# cdh.net
KiCad netlist of a schematic drawn in Altium Designer
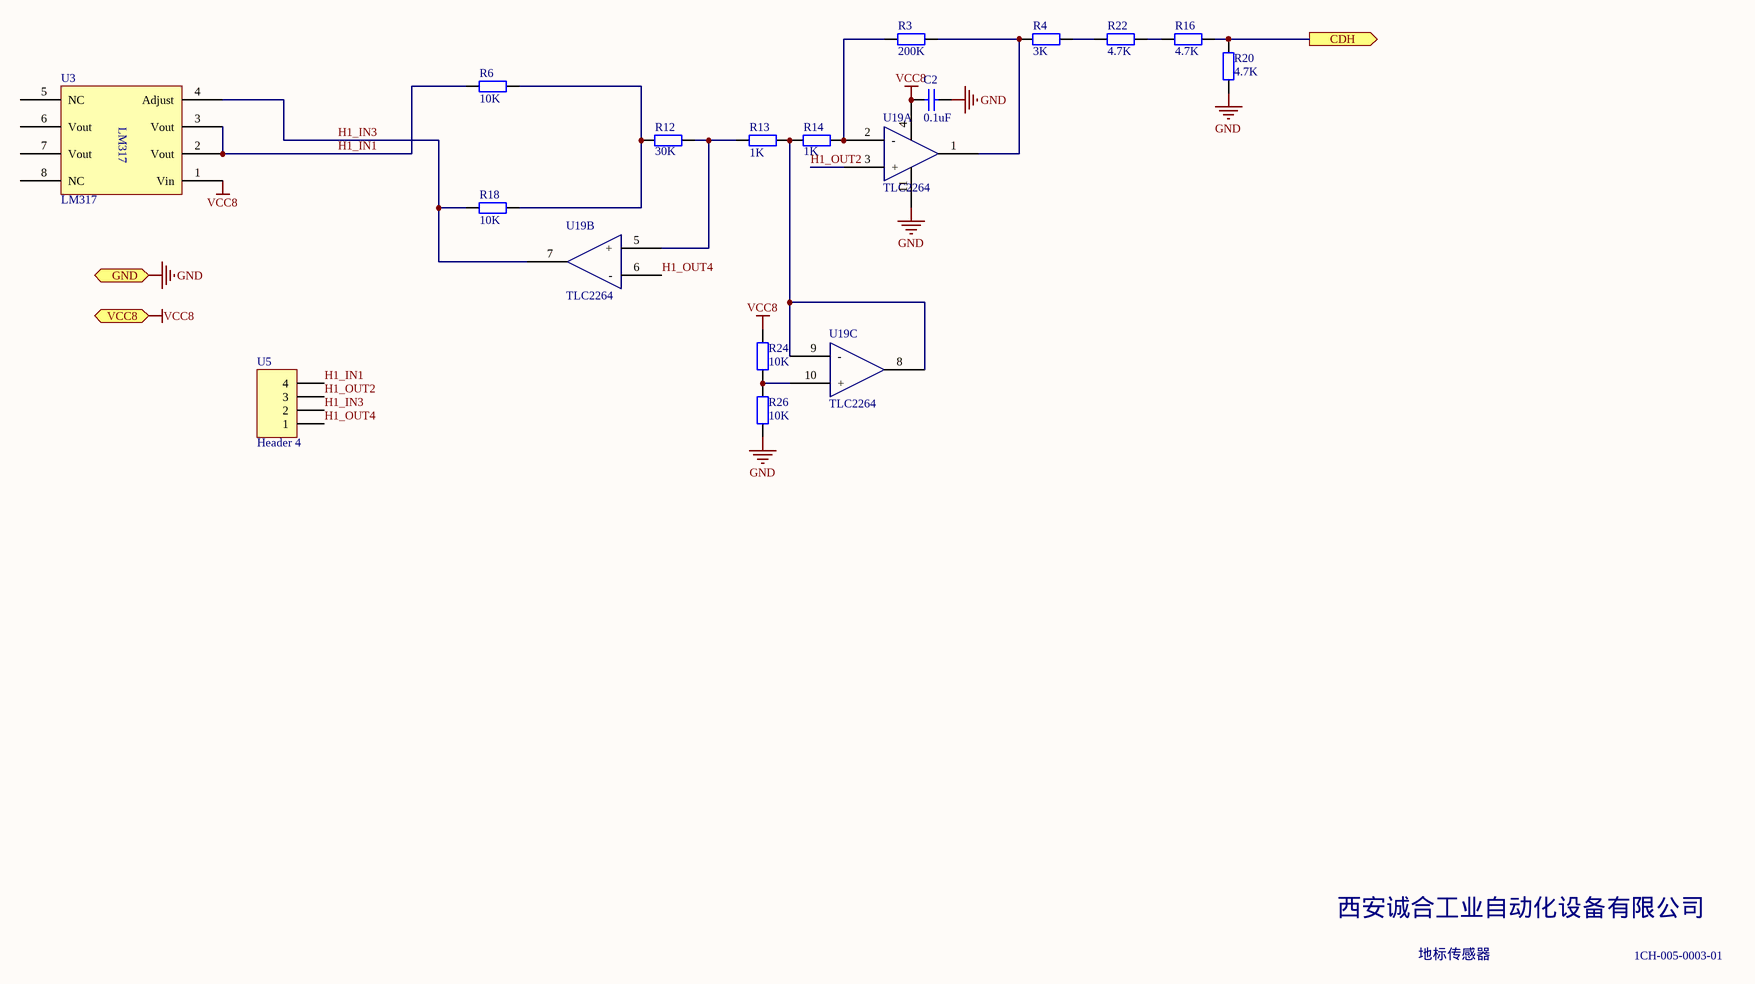
[diagram p0: cdh.SchDoc]

(export (version "E")
  (design (tool "Eeschema 10.0.6"))
  (components
    (comp (ref "C2")
      (value "0.1uF")
      (footprint "C0805")
      (description "Capacitor (Semiconductor SIM Model)")
      (fields (field (name "PUBLISHER") "Altium Limited"))
      (libsource (lib "Miscellaneous Devices") (part "Cap Semi"))
    )
    (comp (ref "R3")
      (value "200K")
      (footprint "0805")
      (description "Resistor")
      (fields (field (name "PUBLISHER") "Altium Limited"))
      (libsource (lib "Miscellaneous Devices") (part "Res2"))
    )
    (comp (ref "R4")
      (value "3K")
      (footprint "0805")
      (description "Resistor")
      (fields (field (name "PUBLISHER") "Altium Limited"))
      (libsource (lib "Miscellaneous Devices") (part "Res2"))
    )
    (comp (ref "R6")
      (value "10K")
      (footprint "0805")
      (description "Resistor")
      (fields (field (name "PUBLISHER") "Altium Limited"))
      (libsource (lib "Miscellaneous Devices") (part "Res2"))
    )
    (comp (ref "R12")
      (value "30K")
      (footprint "0805")
      (description "Resistor")
      (fields (field (name "PUBLISHER") "Altium Limited"))
      (libsource (lib "Miscellaneous Devices") (part "Res2"))
    )
    (comp (ref "R13")
      (value "1K")
      (footprint "0805")
      (description "Resistor")
      (fields (field (name "PUBLISHER") "Altium Limited"))
      (libsource (lib "Miscellaneous Devices") (part "Res2"))
    )
    (comp (ref "R14")
      (value "1K")
      (footprint "0805")
      (description "Resistor")
      (fields (field (name "PUBLISHER") "Altium Limited"))
      (libsource (lib "") (part "Res2_2"))
    )
    (comp (ref "R16")
      (value "4.7K")
      (footprint "0603")
      (description "Resistor")
      (fields (field (name "PUBLISHER") "Altium Limited"))
      (libsource (lib "Miscellaneous Devices") (part "Res2"))
    )
    (comp (ref "R18")
      (value "10K")
      (footprint "0805")
      (description "Resistor")
      (fields (field (name "PUBLISHER") "Altium Limited"))
      (libsource (lib "Miscellaneous Devices") (part "Res2"))
    )
    (comp (ref "R20")
      (value "4.7K")
      (footprint "0603")
      (description "Resistor")
      (fields (field (name "PUBLISHER") "Altium Limited"))
      (libsource (lib "") (part "Res2_1"))
    )
    (comp (ref "R22")
      (value "4.7K")
      (footprint "0805")
      (description "Resistor")
      (fields (field (name "PUBLISHER") "Altium Limited"))
      (libsource (lib "Miscellaneous Devices") (part "Res2"))
    )
    (comp (ref "R24")
      (value "10K")
      (footprint "0805")
      (description "Resistor")
      (fields (field (name "PUBLISHER") "Altium Limited"))
      (libsource (lib "") (part "Res2_1"))
    )
    (comp (ref "R26")
      (value "10K")
      (footprint "0805")
      (description "Resistor")
      (fields (field (name "PUBLISHER") "Altium Limited"))
      (libsource (lib "") (part "Res2_1"))
    )
    (comp (ref "U3") (value "LM317") (footprint "SO-8") (libsource (lib "磁导航") (part "LM317")))
    (comp (ref "U5")
      (value "Header 4")
      (footprint "PIN4")
      (description "Header, 4-Pin")
      (fields (field (name "PUBLISHER") "Altium Limited"))
      (libsource (lib "Miscellaneous Connectors") (part "Header 4"))
    )
    (comp (ref "U19") (value "TLC2264") (footprint "TSSOP14") (libsource (lib "EXPLORER") (part "TLC2264")))
  )
  (nets
    (net (code "1") (name "/CDH") (class "Default")
      (node (ref "R16") (pin "2") (pinfunction "2_2") (pintype "passive"))
      (node (ref "R20") (pin "2") (pinfunction "2_2") (pintype "passive"))
    )
    (net (code "2") (name "/H1_IN1") (class "Default")
      (node (ref "R6") (pin "1") (pinfunction "1_1") (pintype "passive"))
      (node (ref "U3") (pin "2") (pinfunction "Vout_2") (pintype "passive"))
      (node (ref "U3") (pin "3") (pinfunction "Vout_3") (pintype "passive"))
      (node (ref "U5") (pin "4") (pinfunction "4_4") (pintype "passive"))
    )
    (net (code "3") (name "/H1_IN3") (class "Default")
      (node (ref "R18") (pin "1") (pinfunction "1_1") (pintype "passive"))
      (node (ref "U19") (pin "7") (pinfunction "2OUT_7") (pintype "passive"))
      (node (ref "U3") (pin "4") (pinfunction "Adjust_4") (pintype "passive"))
      (node (ref "U5") (pin "2") (pinfunction "2_2") (pintype "passive"))
    )
    (net (code "4") (name "/H1_OUT2") (class "Default")
      (node (ref "U19") (pin "3") (pinfunction "+_3") (pintype "passive"))
      (node (ref "U5") (pin "3") (pinfunction "3_3") (pintype "passive"))
    )
    (net (code "5") (name "/H1_OUT4") (class "Default")
      (node (ref "U19") (pin "6") (pinfunction "-_6") (pintype "passive"))
      (node (ref "U5") (pin "1") (pinfunction "1_1") (pintype "passive"))
    )
    (net (code "6") (name "GND") (class "Default")
      (node (ref "C2") (pin "1") (pinfunction "1_1") (pintype "passive"))
      (node (ref "R20") (pin "1") (pinfunction "1_1") (pintype "passive"))
      (node (ref "R26") (pin "1") (pinfunction "1_1") (pintype "passive"))
      (node (ref "U19") (pin "11") (pinfunction "GND_11") (pintype "passive"))
    )
    (net (code "7") (name "Net-(R12-Pad1)") (class "Default")
      (node (ref "R12") (pin "1") (pinfunction "1_1") (pintype "passive"))
      (node (ref "R18") (pin "2") (pinfunction "2_2") (pintype "passive"))
      (node (ref "R6") (pin "2") (pinfunction "2_2") (pintype "passive"))
    )
    (net (code "8") (name "Net-(R16-Pad1)") (class "Default")
      (node (ref "R16") (pin "1") (pinfunction "1_1") (pintype "passive"))
      (node (ref "R22") (pin "2") (pinfunction "2_2") (pintype "passive"))
    )
    (net (code "9") (name "Net-(R22-Pad1)") (class "Default")
      (node (ref "R22") (pin "1") (pinfunction "1_1") (pintype "passive"))
      (node (ref "R4") (pin "2") (pinfunction "2_2") (pintype "passive"))
    )
    (net (code "10") (name "Net-(U19A--)") (class "Default")
      (node (ref "R14") (pin "1") (pinfunction "1_1") (pintype "passive"))
      (node (ref "R3") (pin "1") (pinfunction "1_1") (pintype "passive"))
      (node (ref "U19") (pin "2") (pinfunction "-_2") (pintype "passive"))
    )
    (net (code "11") (name "Net-(U19A-1OUT)") (class "Default")
      (node (ref "R3") (pin "2") (pinfunction "2_2") (pintype "passive"))
      (node (ref "R4") (pin "1") (pinfunction "1_1") (pintype "passive"))
      (node (ref "U19") (pin "1") (pinfunction "1OUT_1") (pintype "passive"))
    )
    (net (code "12") (name "Net-(U19B-+)") (class "Default")
      (node (ref "R12") (pin "2") (pinfunction "2_2") (pintype "passive"))
      (node (ref "R13") (pin "1") (pinfunction "1_1") (pintype "passive"))
      (node (ref "U19") (pin "5") (pinfunction "+_5") (pintype "passive"))
    )
    (net (code "13") (name "Net-(U19C-+)") (class "Default")
      (node (ref "R24") (pin "1") (pinfunction "1_1") (pintype "passive"))
      (node (ref "R26") (pin "2") (pinfunction "2_2") (pintype "passive"))
      (node (ref "U19") (pin "10") (pinfunction "+_10") (pintype "passive"))
    )
    (net (code "14") (name "Net-(U19C--)") (class "Default")
      (node (ref "R13") (pin "2") (pinfunction "2_2") (pintype "passive"))
      (node (ref "R14") (pin "2") (pinfunction "2_2") (pintype "passive"))
      (node (ref "U19") (pin "8") (pinfunction "3OUT_8") (pintype "passive"))
      (node (ref "U19") (pin "9") (pinfunction "-_9") (pintype "passive"))
    )
    (net (code "15") (name "VCC8") (class "Default")
      (node (ref "C2") (pin "2") (pinfunction "2_2") (pintype "passive"))
      (node (ref "R24") (pin "2") (pinfunction "2_2") (pintype "passive"))
      (node (ref "U19") (pin "4") (pinfunction "VCC_4") (pintype "passive"))
      (node (ref "U3") (pin "1") (pinfunction "Vin_1") (pintype "passive"))
    )
    (net (code "16") (name "unconnected-(U3-NC-Pad5)") (class "Default")
      (node (ref "U3") (pin "5") (pinfunction "NC_5") (pintype "passive"))
    )
    (net (code "17") (name "unconnected-(U3-NC-Pad8)") (class "Default")
      (node (ref "U3") (pin "8") (pinfunction "NC_8") (pintype "passive"))
    )
    (net (code "18") (name "unconnected-(U3-Vout-Pad6)") (class "Default")
      (node (ref "U3") (pin "6") (pinfunction "Vout_6") (pintype "passive"))
    )
    (net (code "19") (name "unconnected-(U3-Vout-Pad7)") (class "Default")
      (node (ref "U3") (pin "7") (pinfunction "Vout_7") (pintype "passive"))
    )
  )
)
